# LPFADC.net
KiCad netlist of a schematic drawn in Altium Designer
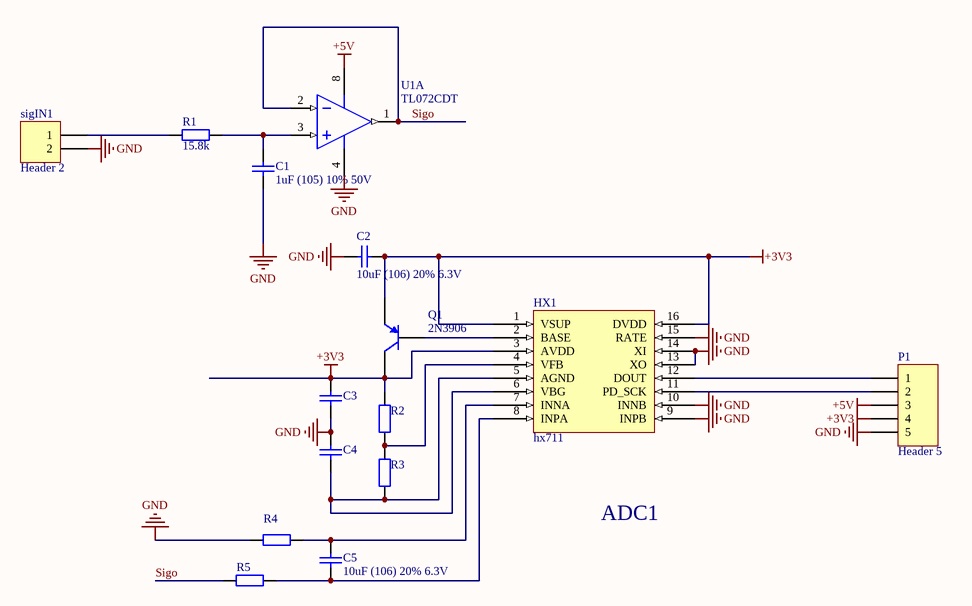
[diagram p0: LPFADC.SchDoc]

(export (version "E")
  (design (tool "Eeschema 10.0.6"))
  (components
    (comp (ref "C1")
      (value "1uF (105) 10% 50V")
      (footprint "0805_C")
      (description "贴片电容")
      (libsource (lib "Miscellaneous Devices LC") (part "0805 1uF (105) 10% 50V"))
    )
    (comp (ref "C2")
      (value "10uF (106) 20% 6.3V")
      (footprint "0402_C")
      (description "贴片电容")
      (libsource (lib "Miscellaneous Devices LC") (part "0402 10uF (106) 20% 6.3V"))
    )
    (comp (ref "C3")
      (value "10uF (106) 20% 6.3V")
      (footprint "0402_C")
      (description "贴片电容")
      (libsource (lib "Miscellaneous Devices LC") (part "0402 10uF (106) 20% 6.3V"))
    )
    (comp (ref "C4")
      (value "10uF (106) 20% 6.3V")
      (footprint "0402_C")
      (description "贴片电容")
      (libsource (lib "Miscellaneous Devices LC") (part "0402 10uF (106) 20% 6.3V"))
    )
    (comp (ref "C5")
      (value "10uF (106) 20% 6.3V")
      (footprint "0402_C")
      (description "贴片电容")
      (libsource (lib "Miscellaneous Devices LC") (part "0402 10uF (106) 20% 6.3V"))
    )
    (comp (ref "HX1") (value "hx711") (footprint "HX711") (libsource (lib "Schlib1") (part "hx711")))
    (comp (ref "P1")
      (value "Header 5")
      (footprint "HDR1X5")
      (description "Header, 5-Pin")
      (fields (field (name "PUBLISHER") "Altium Limited"))
      (libsource (lib "Miscellaneous Connectors") (part "Header 5"))
    )
    (comp (ref "Q1")
      (value "2N3906")
      (footprint "TO-92A")
      (description "PNP General Purpose Amplifier")
      (fields (field (name "PUBLISHER") "Altium Limited"))
      (libsource (lib "Miscellaneous Devices") (part "2N3906"))
    )
    (comp (ref "R1")
      (value "15.8k")
      (footprint "0805_R")
      (description "贴片电阻")
      (libsource (lib "Miscellaneous Devices LC") (part "0805 330KΩ (3303) 1%"))
    )
    (comp (ref "R2")
      (value "10KΩ (1002) ±1%")
      (footprint "0603_R")
      (description "贴片电阻")
      (libsource (lib "Miscellaneous Devices LC") (part "0603 10KΩ (1002) 1%"))
    )
    (comp (ref "R3")
      (value "10KΩ (1002) ±1%")
      (footprint "0603_R")
      (description "贴片电阻")
      (libsource (lib "Miscellaneous Devices LC") (part "0603 10KΩ (1002) 1%"))
    )
    (comp (ref "R4")
      (value "1KΩ (1002) ±1%")
      (footprint "0603_R")
      (description "贴片电阻")
      (libsource (lib "") (part "0603 10KΩ (1002) 1%_1"))
    )
    (comp (ref "R5")
      (value "1KΩ (1002) ±1%")
      (footprint "0603_R")
      (description "贴片电阻")
      (libsource (lib "") (part "0603 10KΩ (1002) 1%_1"))
    )
    (comp (ref "sigIN1")
      (value "Header 2")
      (footprint "HDR1X2")
      (description "Header, 2-Pin")
      (fields (field (name "PUBLISHER") "Altium Limited"))
      (libsource (lib "Miscellaneous Connectors") (part "Header 2"))
    )
    (comp (ref "U1")
      (value "TL072CDT")
      (footprint "SOIC-8_150mil")
      (description "运放")
      (libsource (lib "Miscellaneous Devices LC") (part "TL072CDT_[C6961]"))
    )
  )
  (nets
    (net (code "1") (name "+3V3") (class "Default")
      (node (ref "C2") (pin "2") (pinfunction "2_2") (pintype "passive"))
      (node (ref "C3") (pin "1") (pinfunction "1_1") (pintype "passive"))
      (node (ref "HX1") (pin "1") (pinfunction "VSUP_1") (pintype "input"))
      (node (ref "HX1") (pin "16") (pinfunction "DVDD_16") (pintype "input"))
      (node (ref "HX1") (pin "3") (pinfunction "AVDD_3") (pintype "input"))
      (node (ref "P1") (pin "4") (pinfunction "4_4") (pintype "passive"))
      (node (ref "Q1") (pin "1") (pinfunction "E_1") (pintype "passive"))
      (node (ref "Q1") (pin "3") (pinfunction "C_3") (pintype "passive"))
      (node (ref "R2") (pin "2") (pinfunction "2_2") (pintype "passive"))
    )
    (net (code "2") (name "+5V") (class "Default")
      (node (ref "P1") (pin "3") (pinfunction "3_3") (pintype "passive"))
      (node (ref "U1") (pin "8") (pinfunction "V+_8") (pintype "power_in"))
    )
    (net (code "3") (name "/Sigo") (class "Default")
      (node (ref "R5") (pin "2") (pinfunction "2_2") (pintype "passive"))
      (node (ref "U1") (pin "1") (pinfunction "OUT_1") (pintype "output"))
      (node (ref "U1") (pin "2") (pinfunction "IN-_2") (pintype "input"))
    )
    (net (code "4") (name "GND") (class "Default")
      (node (ref "C1") (pin "1") (pinfunction "1_1") (pintype "passive"))
      (node (ref "C2") (pin "1") (pinfunction "1_1") (pintype "passive"))
      (node (ref "C3") (pin "2") (pinfunction "2_2") (pintype "passive"))
      (node (ref "C4") (pin "1") (pinfunction "1_1") (pintype "passive"))
      (node (ref "HX1") (pin "10") (pinfunction "INNB_10") (pintype "input"))
      (node (ref "HX1") (pin "13") (pinfunction "XO_13") (pintype "input"))
      (node (ref "HX1") (pin "14") (pinfunction "XI_14") (pintype "input"))
      (node (ref "HX1") (pin "15") (pinfunction "RATE_15") (pintype "input"))
      (node (ref "HX1") (pin "9") (pinfunction "INPB_9") (pintype "input"))
      (node (ref "P1") (pin "5") (pinfunction "5_5") (pintype "passive"))
      (node (ref "R4") (pin "2") (pinfunction "2_2") (pintype "passive"))
      (node (ref "U1") (pin "4") (pinfunction "V-_4") (pintype "power_in"))
      (node (ref "sigIN1") (pin "2") (pinfunction "2_2") (pintype "passive"))
    )
    (net (code "5") (name "Net-(HX1-AGND)") (class "Default")
      (node (ref "C4") (pin "2") (pinfunction "2_2") (pintype "passive"))
      (node (ref "HX1") (pin "5") (pinfunction "AGND_5") (pintype "input"))
      (node (ref "HX1") (pin "6") (pinfunction "VBG_6") (pintype "input"))
      (node (ref "R3") (pin "1") (pinfunction "1_1") (pintype "passive"))
    )
    (net (code "6") (name "Net-(HX1-BASE)") (class "Default")
      (node (ref "HX1") (pin "2") (pinfunction "BASE_2") (pintype "input"))
      (node (ref "Q1") (pin "2") (pinfunction "B_2") (pintype "passive"))
    )
    (net (code "7") (name "Net-(HX1-DOUT)") (class "Default")
      (node (ref "HX1") (pin "12") (pinfunction "DOUT_12") (pintype "input"))
      (node (ref "P1") (pin "1") (pinfunction "1_1") (pintype "passive"))
    )
    (net (code "8") (name "Net-(HX1-INNA)") (class "Default")
      (node (ref "C5") (pin "1") (pinfunction "1_1") (pintype "passive"))
      (node (ref "HX1") (pin "7") (pinfunction "INNA_7") (pintype "input"))
      (node (ref "R4") (pin "1") (pinfunction "1_1") (pintype "passive"))
    )
    (net (code "9") (name "Net-(HX1-INPA)") (class "Default")
      (node (ref "C5") (pin "2") (pinfunction "2_2") (pintype "passive"))
      (node (ref "HX1") (pin "8") (pinfunction "INPA_8") (pintype "input"))
      (node (ref "R5") (pin "1") (pinfunction "1_1") (pintype "passive"))
    )
    (net (code "10") (name "Net-(HX1-PD_SCK)") (class "Default")
      (node (ref "HX1") (pin "11") (pinfunction "PD_SCK_11") (pintype "input"))
      (node (ref "P1") (pin "2") (pinfunction "2_2") (pintype "passive"))
    )
    (net (code "11") (name "Net-(HX1-VFB)") (class "Default")
      (node (ref "HX1") (pin "4") (pinfunction "VFB_4") (pintype "input"))
      (node (ref "R2") (pin "1") (pinfunction "1_1") (pintype "passive"))
      (node (ref "R3") (pin "2") (pinfunction "2_2") (pintype "passive"))
    )
    (net (code "12") (name "Net-(R1-Pad1)") (class "Default")
      (node (ref "R1") (pin "1") (pinfunction "1_1") (pintype "passive"))
      (node (ref "sigIN1") (pin "1") (pinfunction "1_1") (pintype "passive"))
    )
    (net (code "13") (name "Net-(U1A-IN+)") (class "Default")
      (node (ref "C1") (pin "2") (pinfunction "2_2") (pintype "passive"))
      (node (ref "R1") (pin "2") (pinfunction "2_2") (pintype "passive"))
      (node (ref "U1") (pin "3") (pinfunction "IN+_3") (pintype "input"))
    )
  )
)
